# SCH_TwoStep-OPEN-SOURCE_2024-09-30.net
KiCad netlist of a schematic drawn in EasyEDA
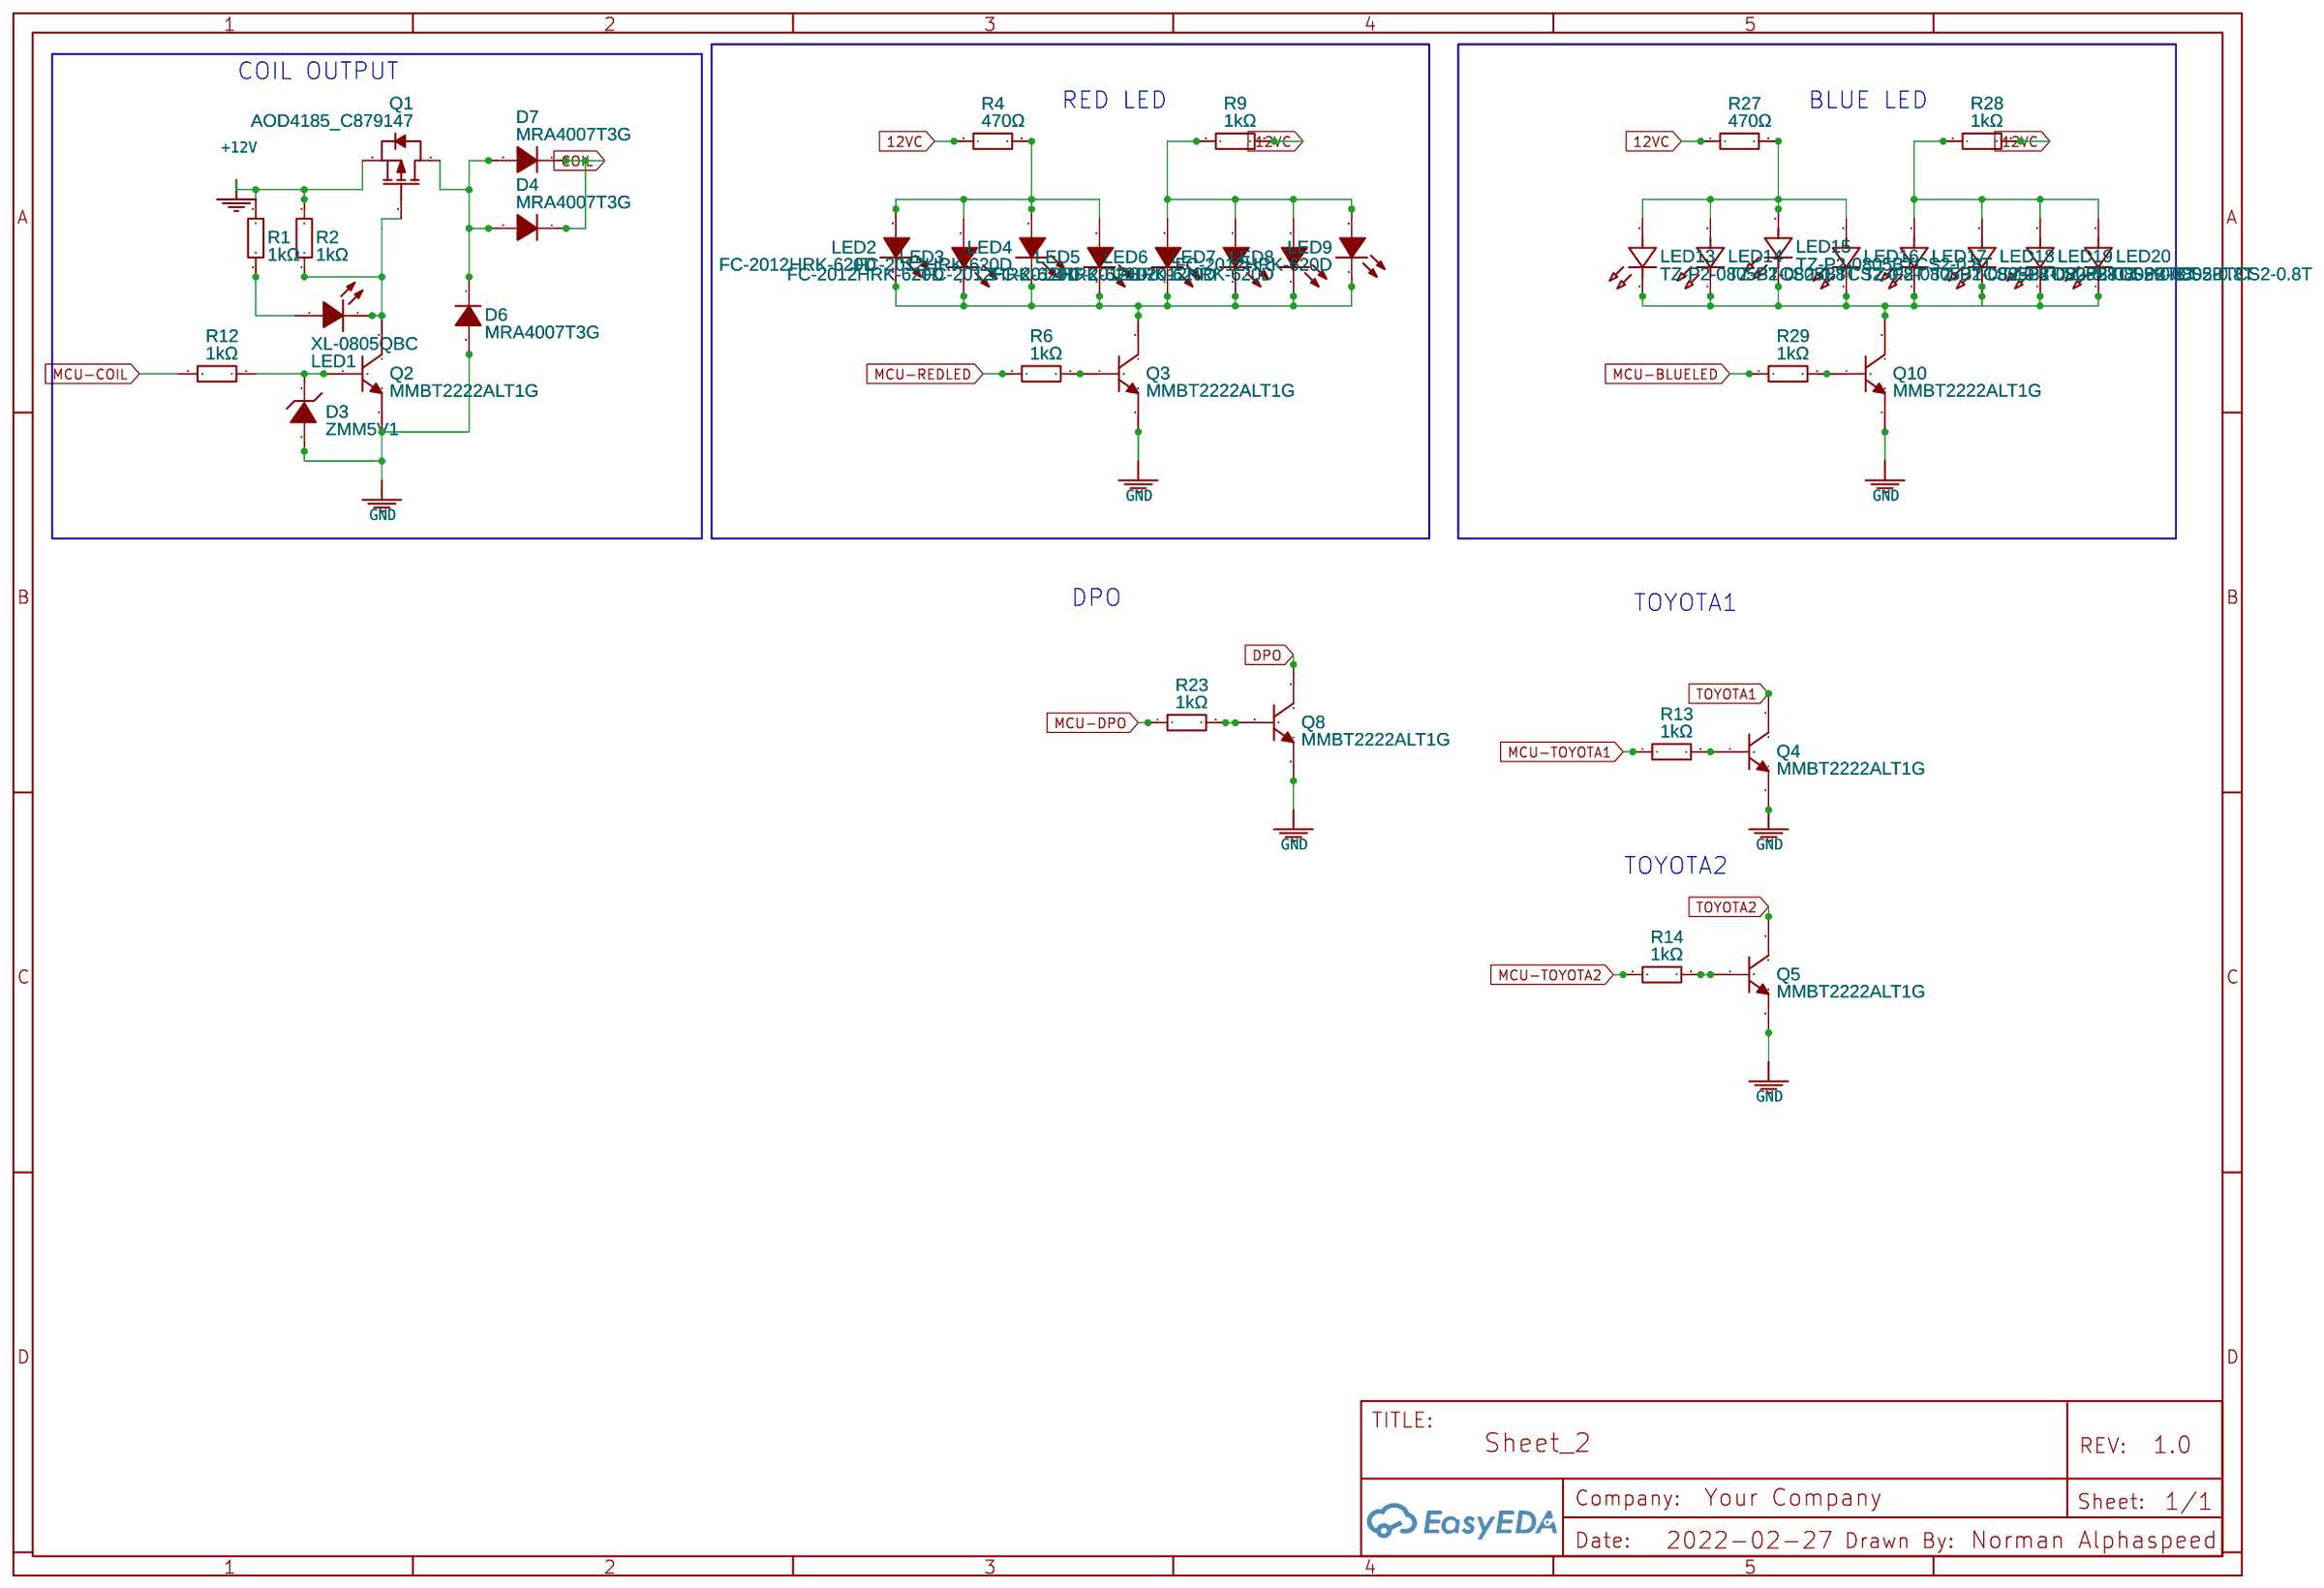
[diagram p0: Outputs]
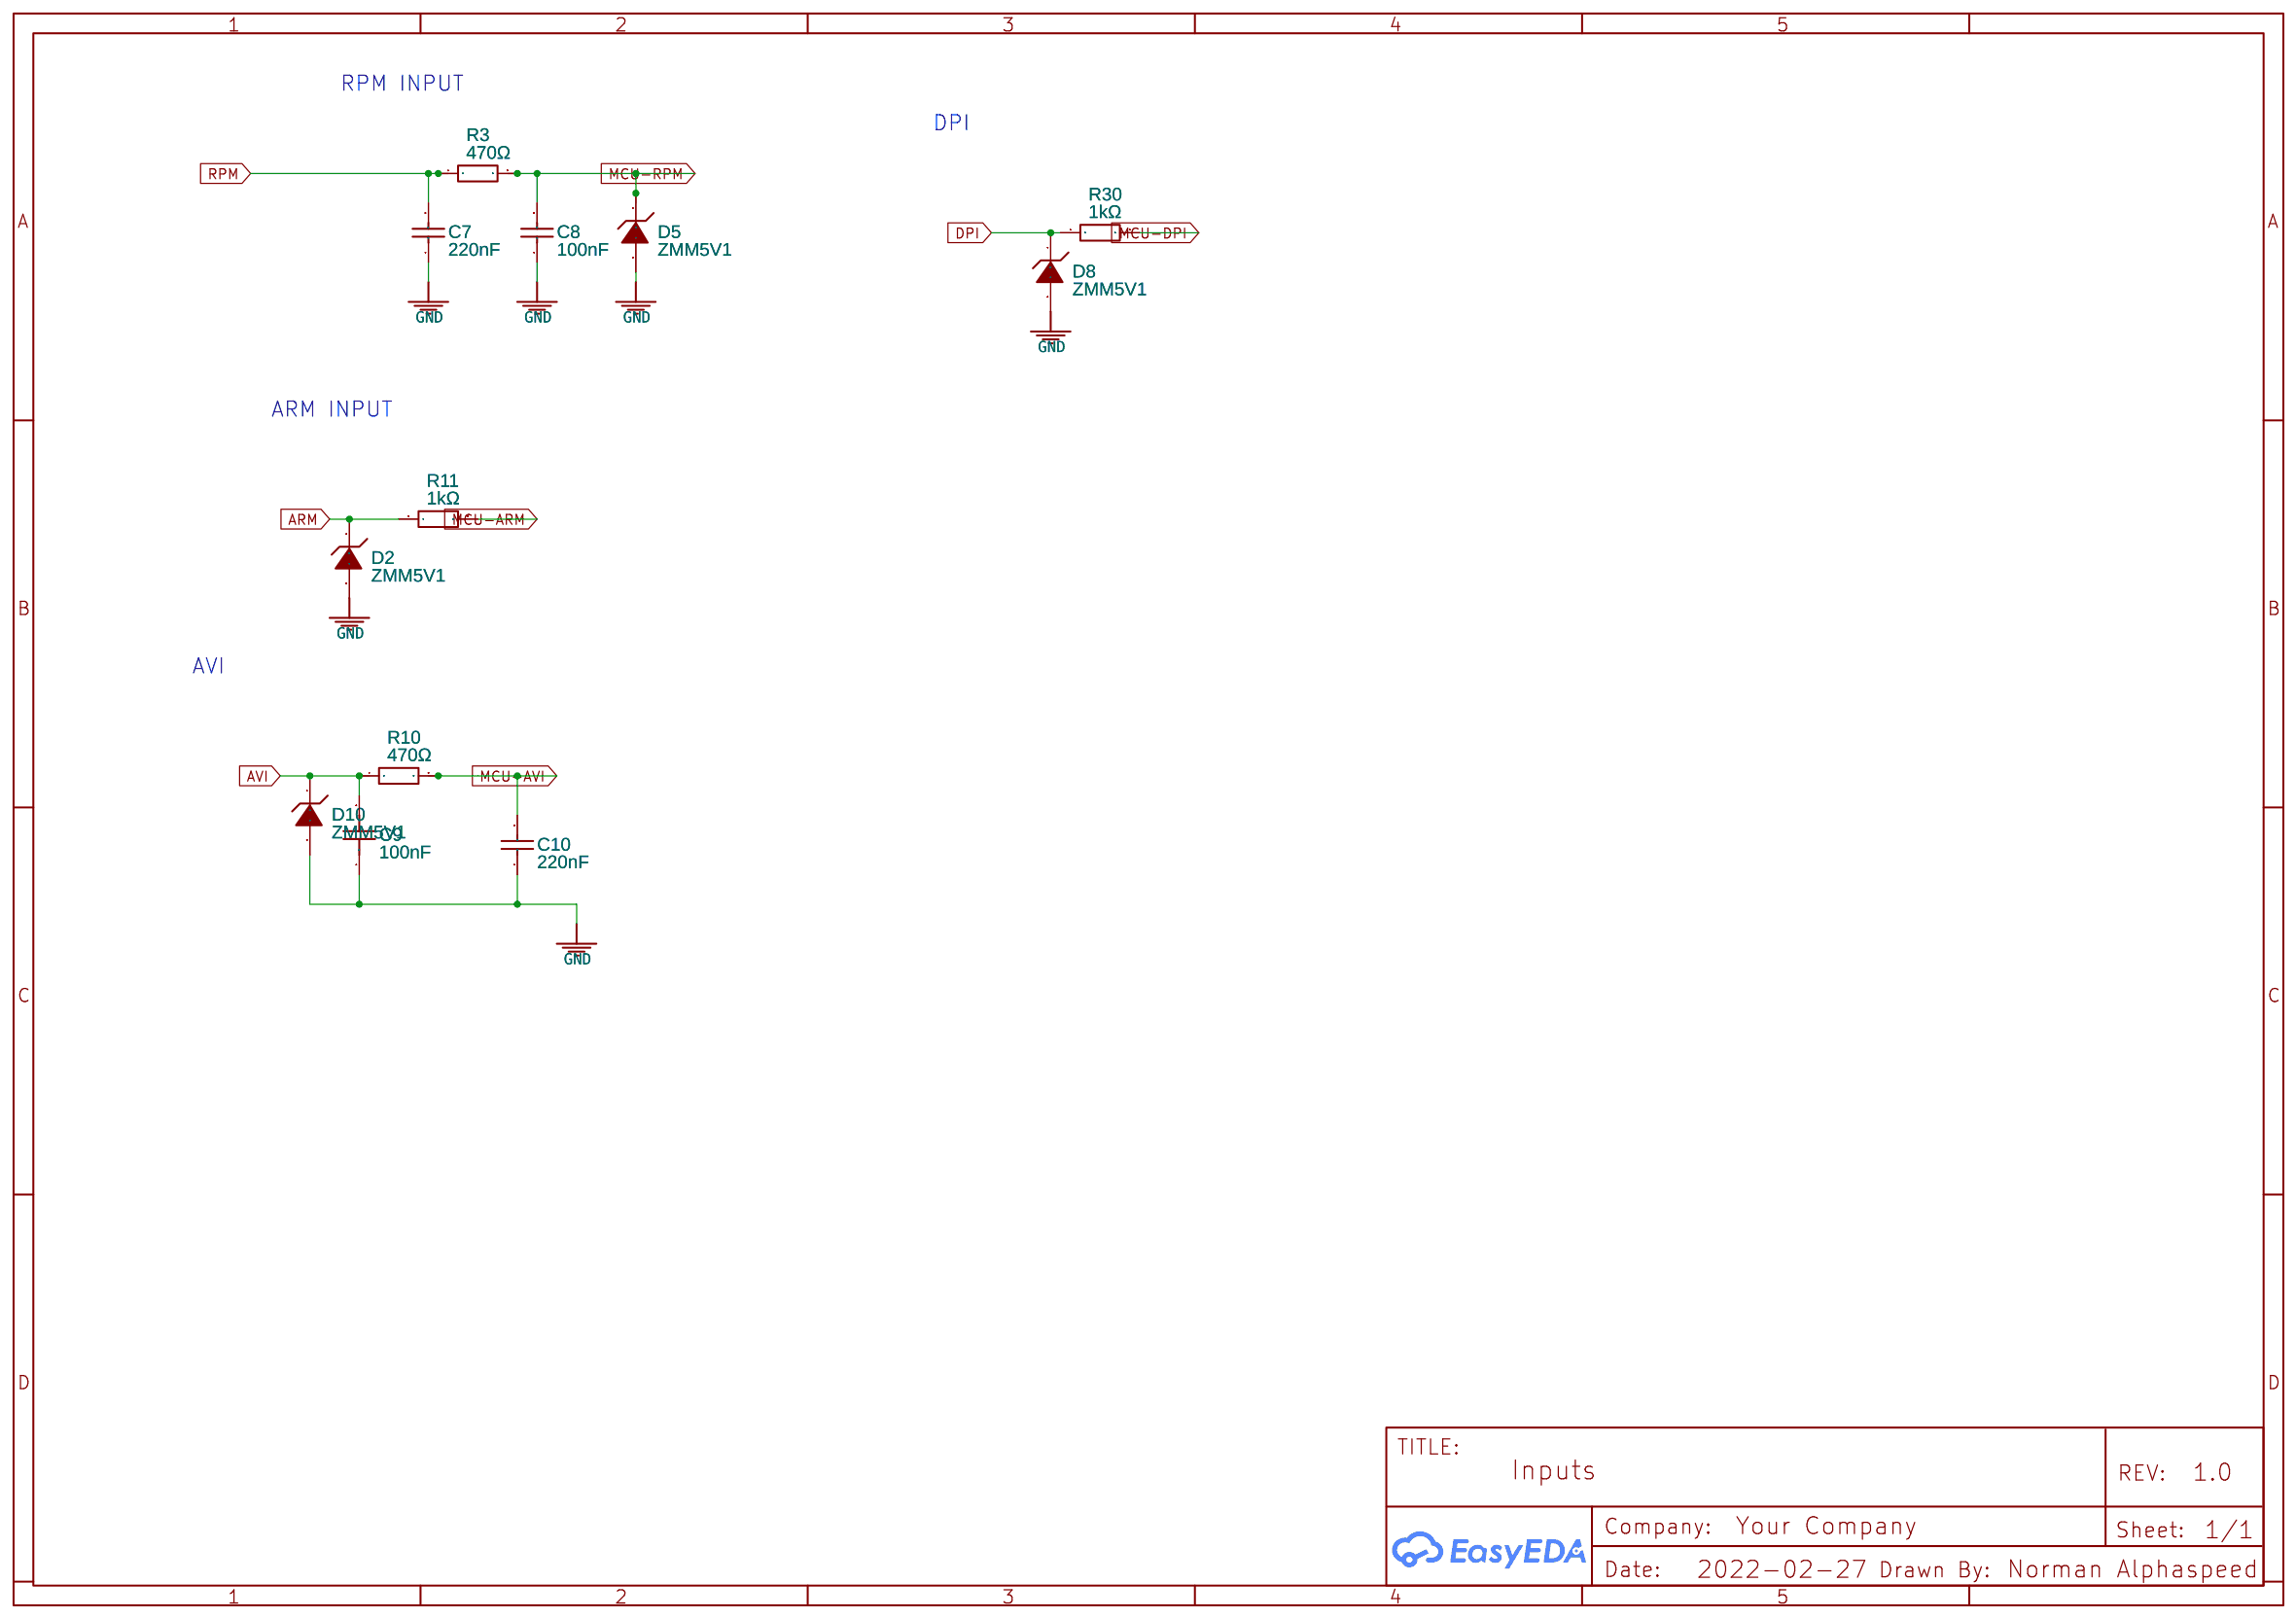
[diagram p1: Inputs]
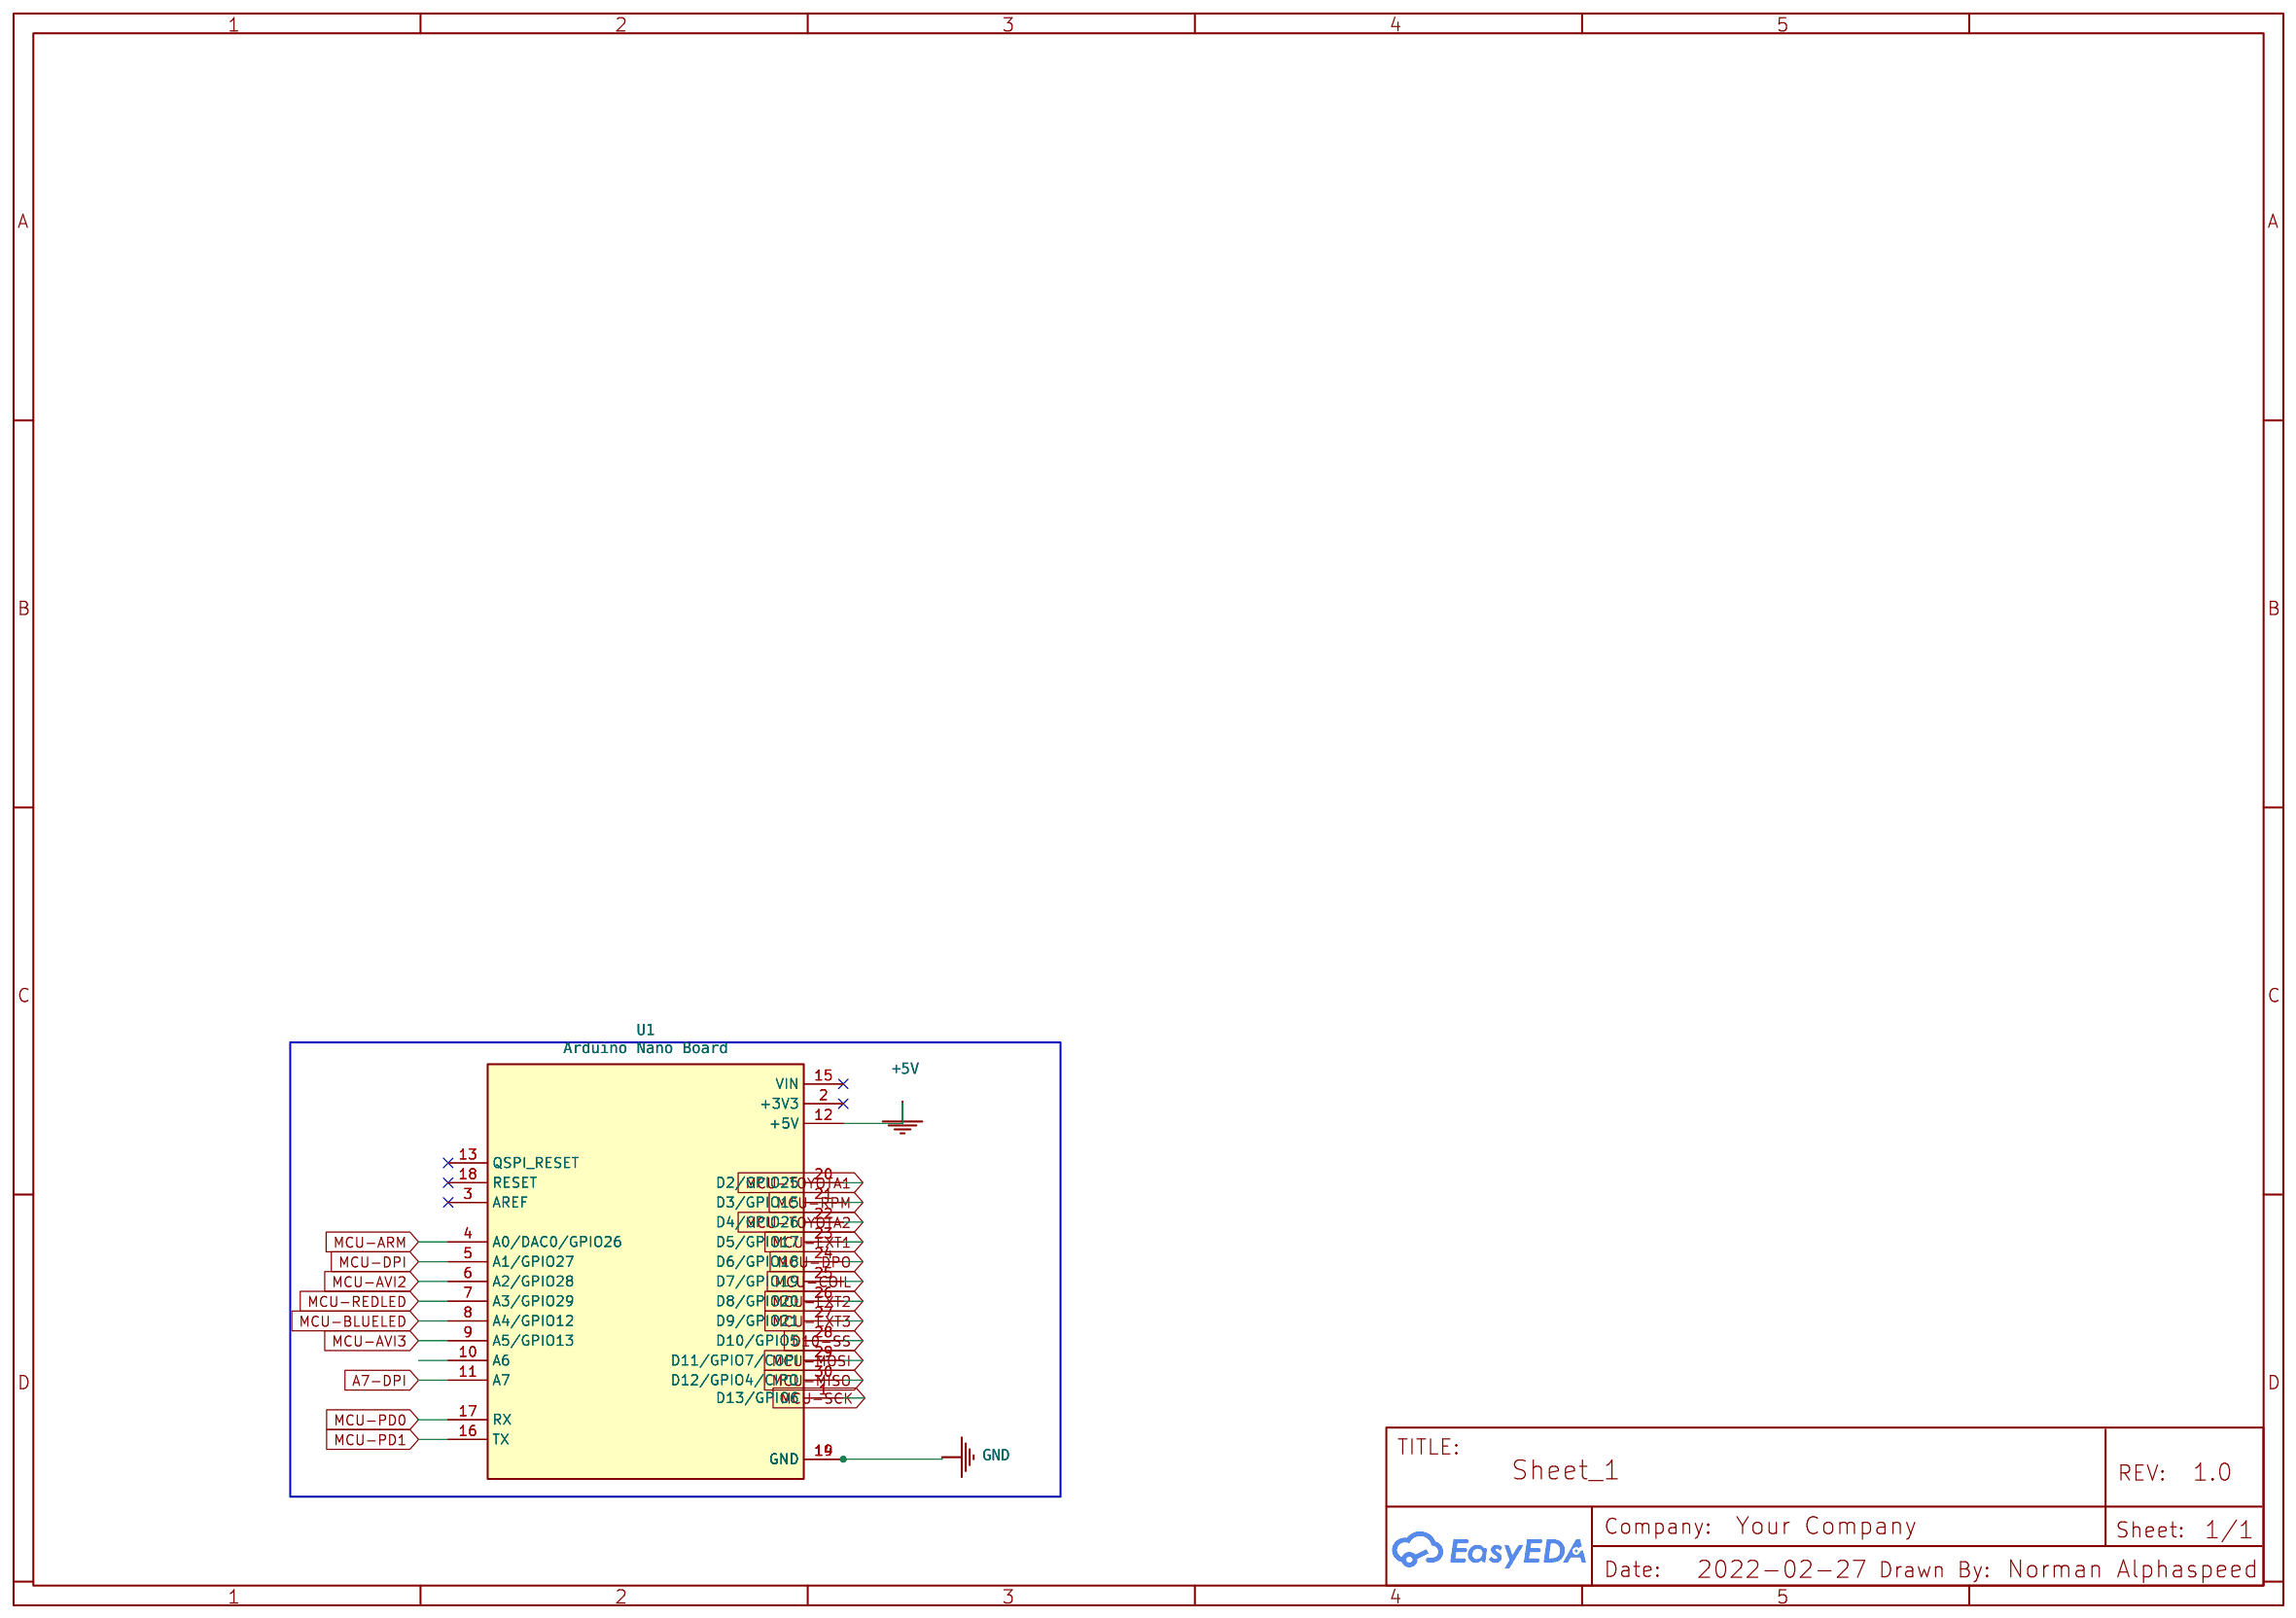
[diagram p2: MCU]
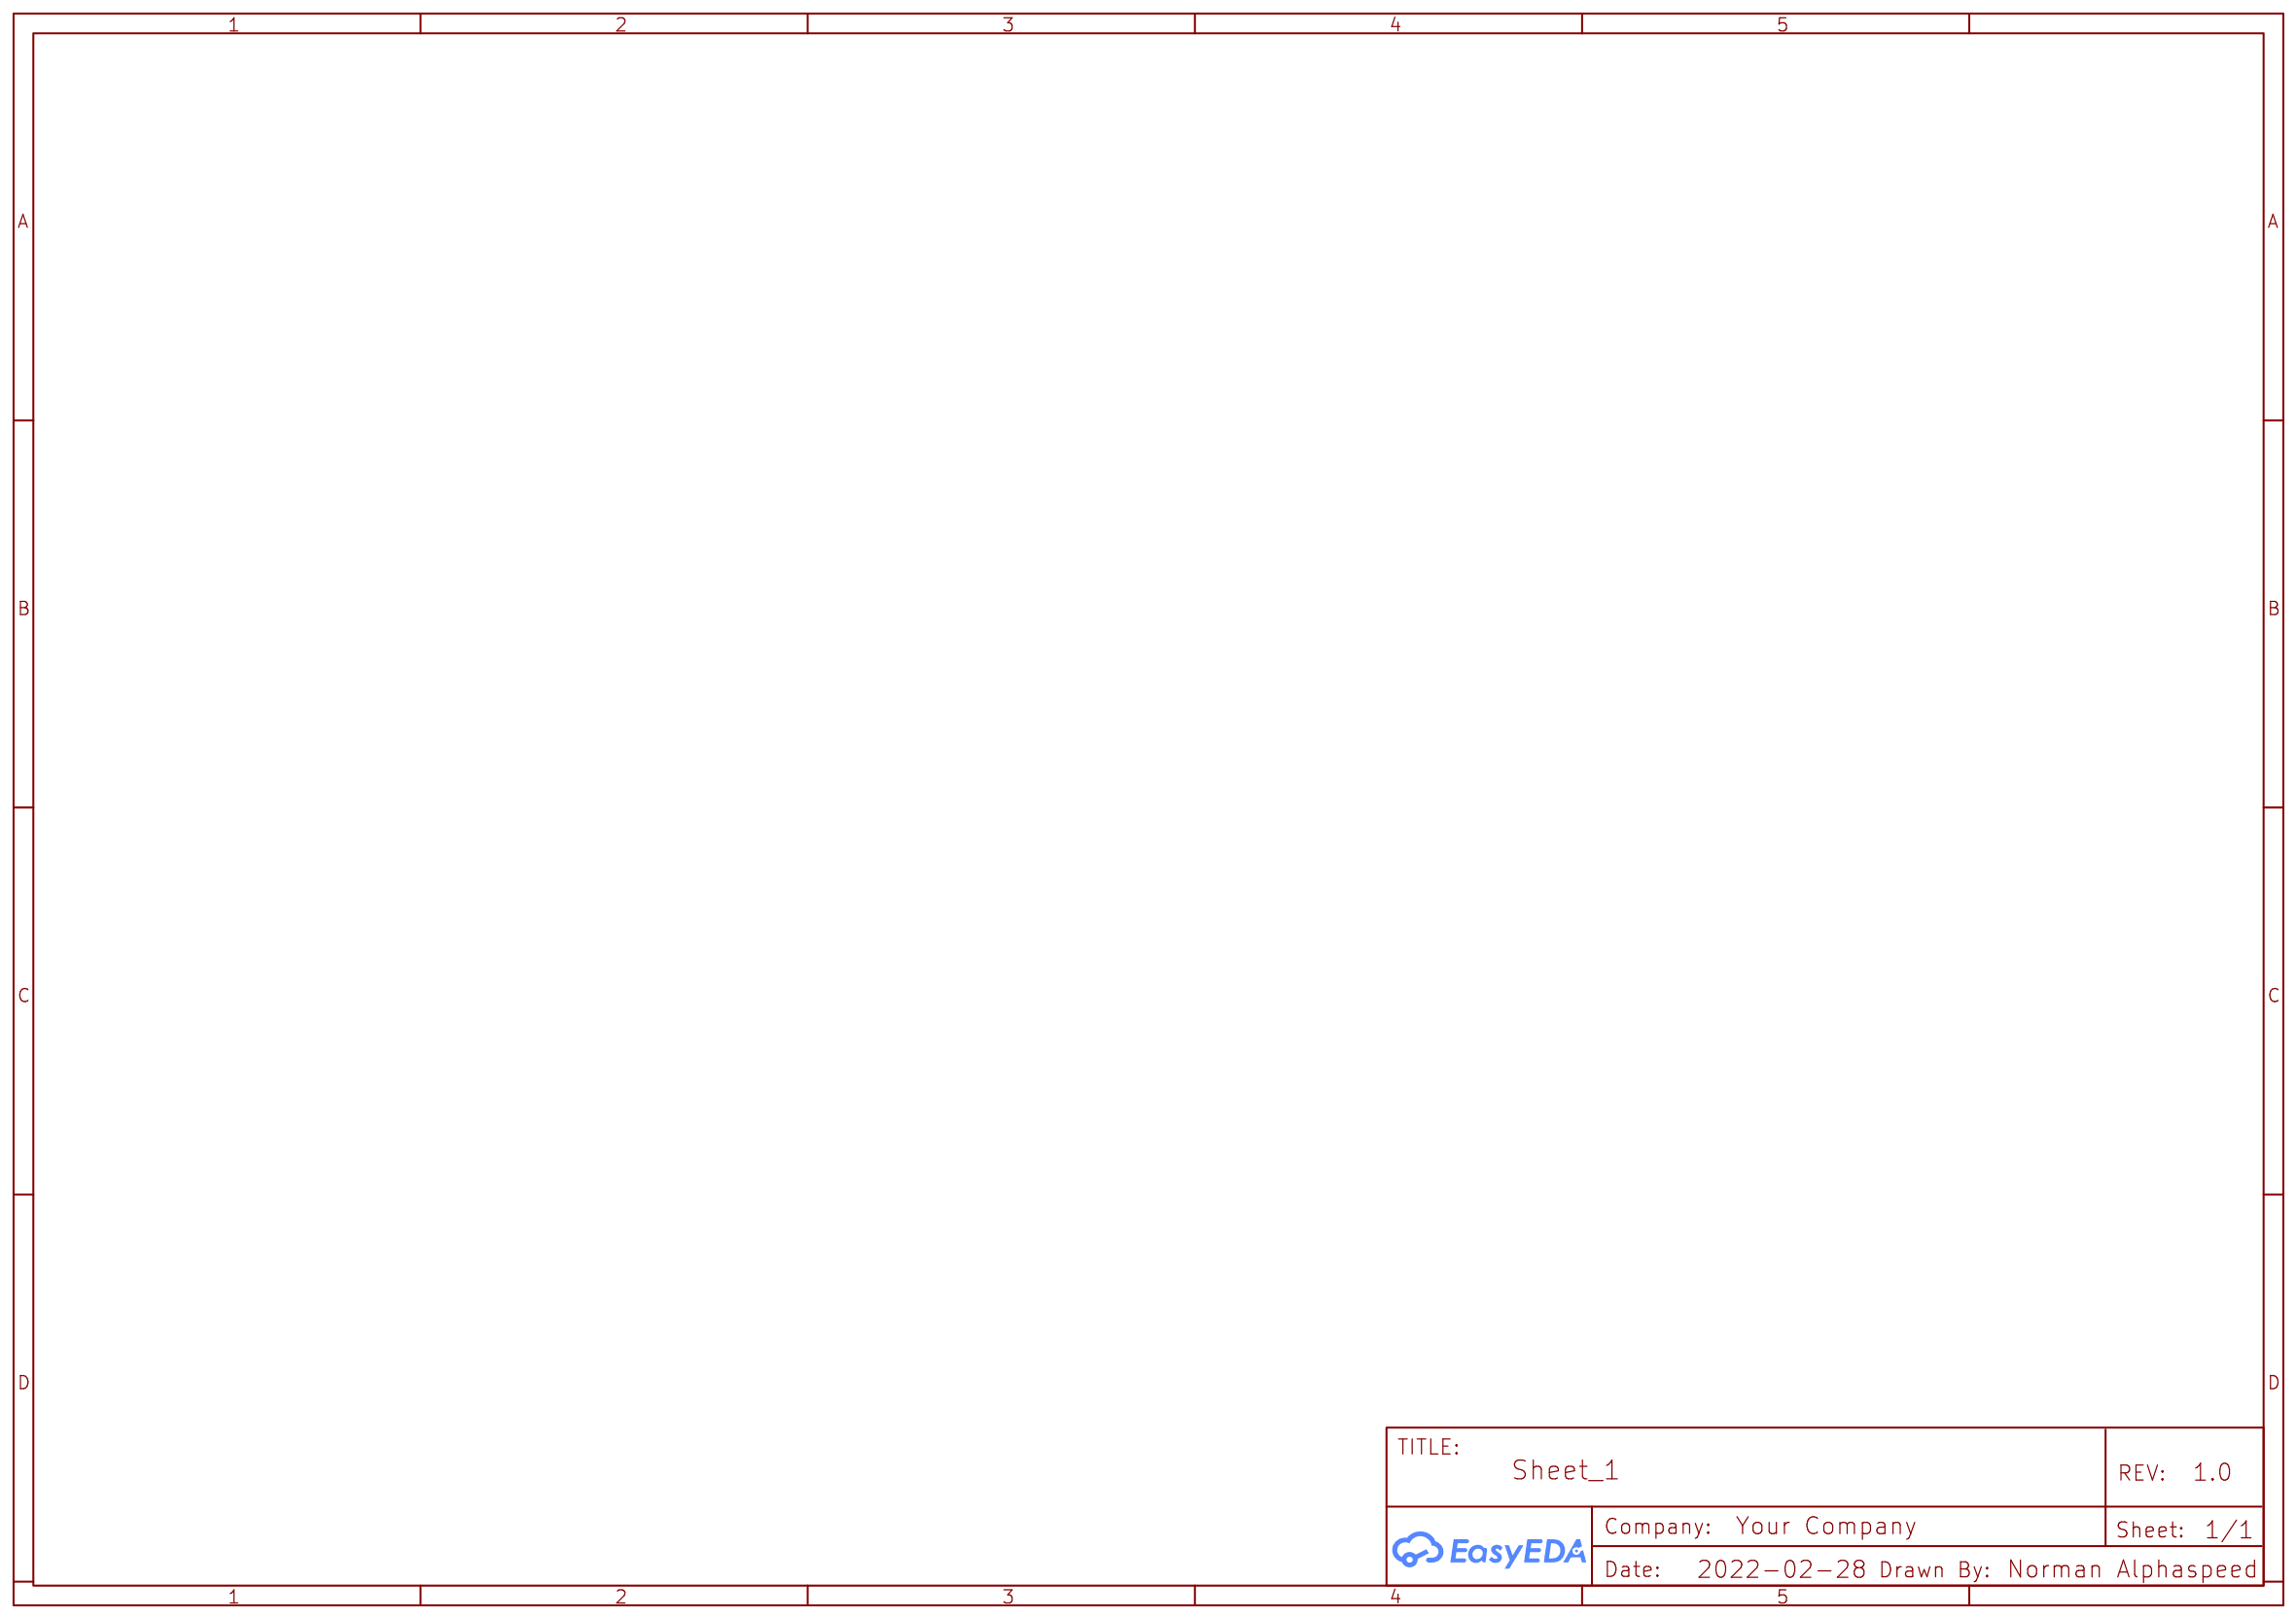
[diagram p3: Comms]
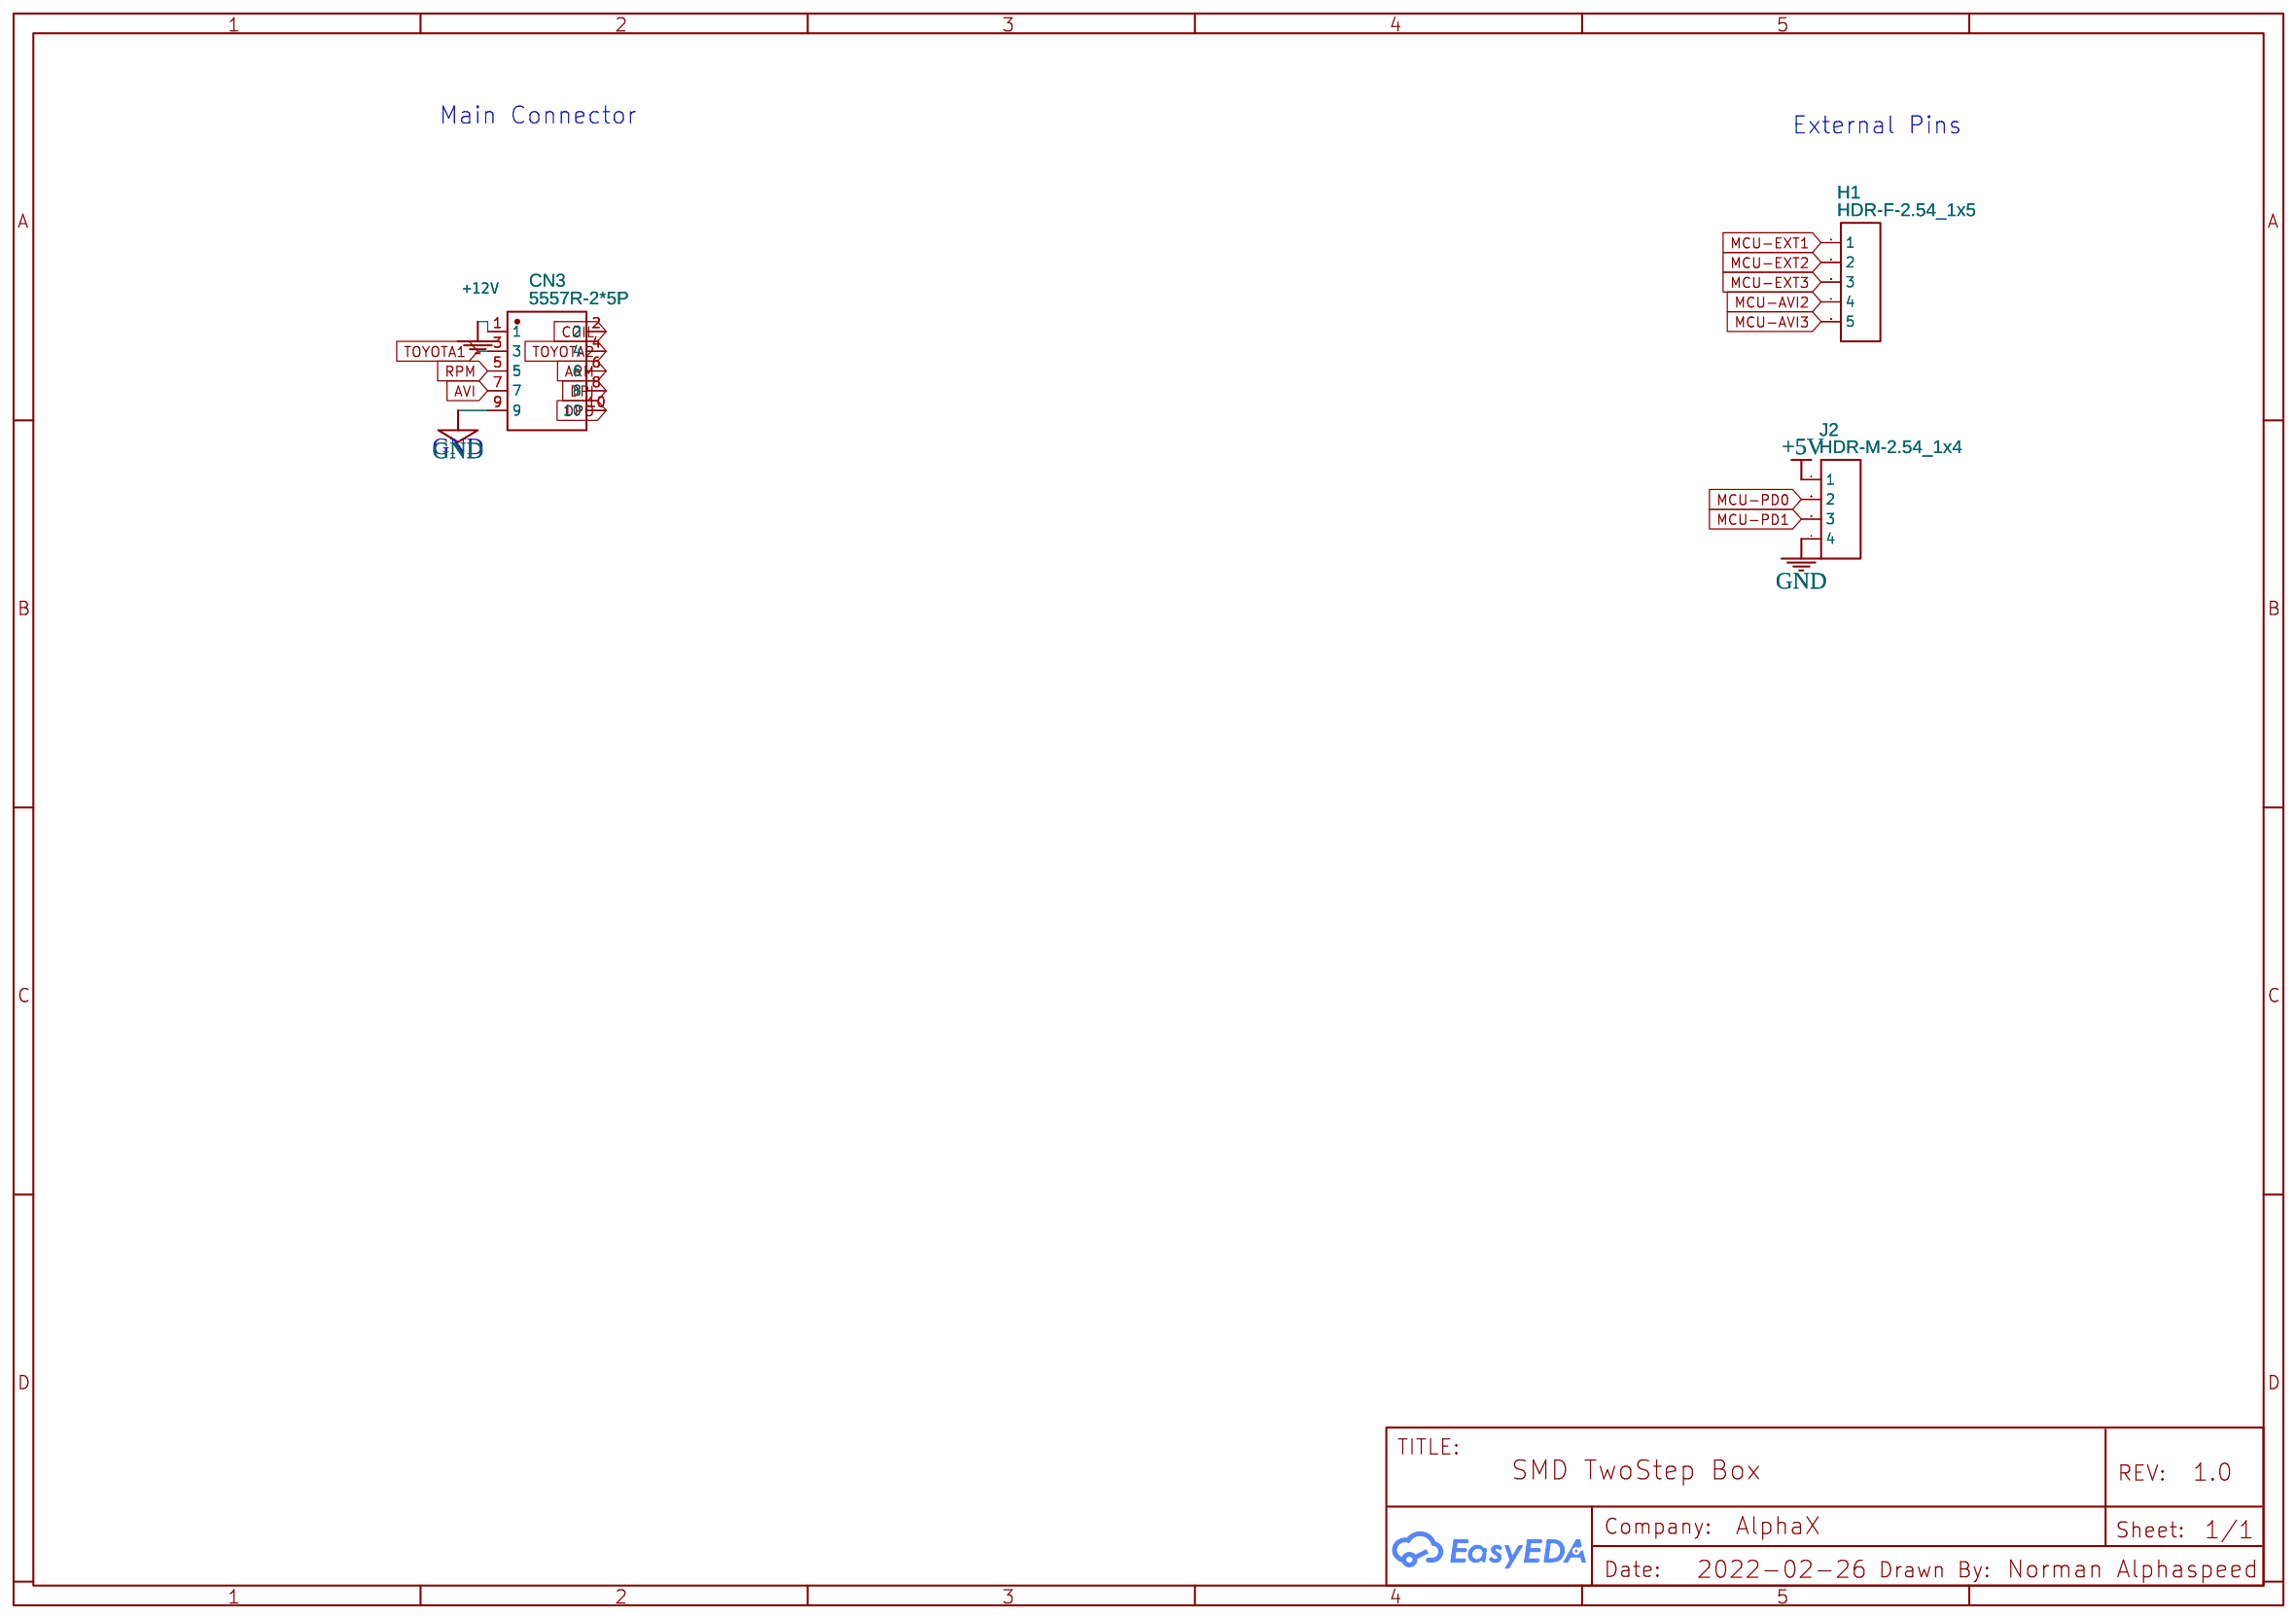
[diagram p4: Connector copy copy]
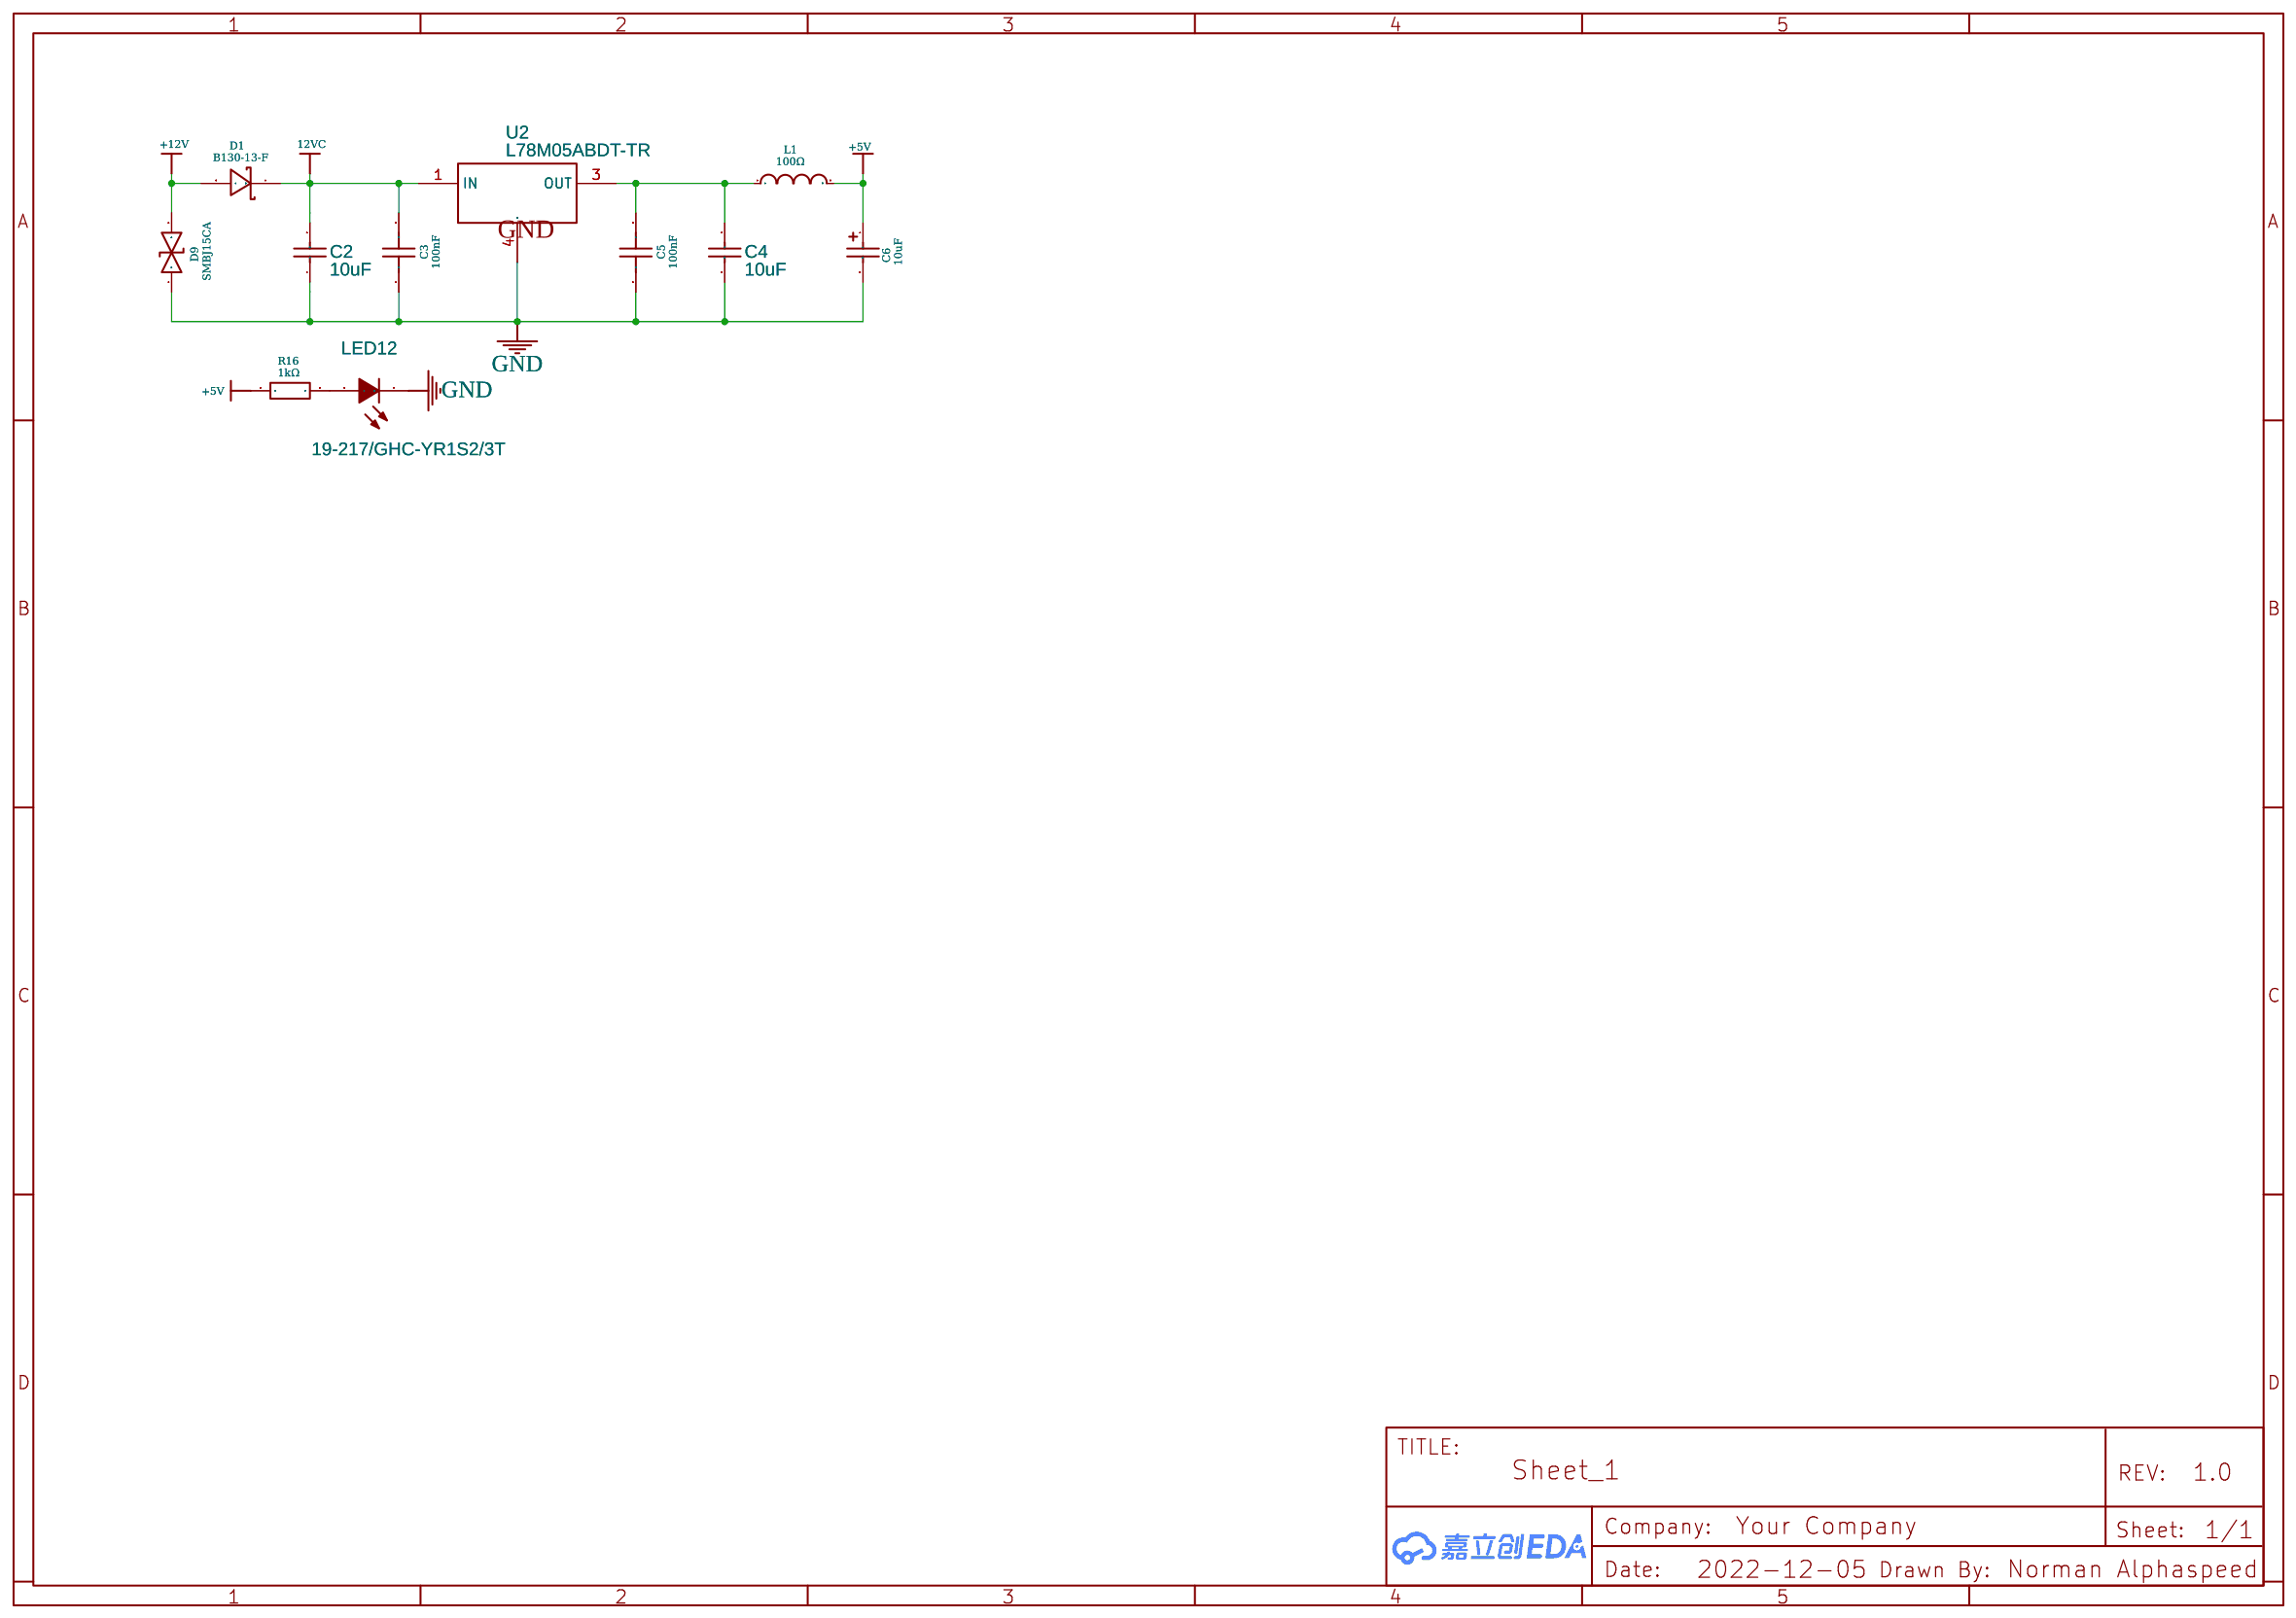
[diagram p5: Power]

(export (version "E")
  (design (tool "Eeschema 10.0.6"))
  (components
    (comp (ref "D3")
      (value "ZMM5V1")
      (fields (field (name "Manufacturer") "SEMTECH"))
      (libsource (lib "") (part "ZMM5V1"))
    )
    (comp (ref "D4")
      (value "MRA4007T3G")
      (fields (field (name "Manufacturer") "ON"))
      (libsource (lib "") (part "MRA4007T3G"))
    )
    (comp (ref "D6")
      (value "MRA4007T3G")
      (fields (field (name "Manufacturer") "ON"))
      (libsource (lib "") (part "MRA4007T3G_1"))
    )
    (comp (ref "D7")
      (value "MRA4007T3G")
      (fields (field (name "Manufacturer") "ON"))
      (libsource (lib "") (part "MRA4007T3G"))
    )
    (comp (ref "LED1")
      (value "XL-0805QBC")
      (fields (field (name "Manufacturer") "KENTO"))
      (libsource (lib "") (part "XL-0805QBC"))
    )
    (comp (ref "LED2")
      (value "FC-2012HRK-620D")
      (fields (field (name "Manufacturer") "NATIONSTAR"))
      (libsource (lib "") (part "FC-2012HRK-620D"))
    )
    (comp (ref "LED3")
      (value "FC-2012HRK-620D")
      (fields (field (name "Manufacturer") "NATIONSTAR"))
      (libsource (lib "") (part "FC-2012HRK-620D"))
    )
    (comp (ref "LED4")
      (value "FC-2012HRK-620D")
      (fields (field (name "Manufacturer") "NATIONSTAR"))
      (libsource (lib "") (part "FC-2012HRK-620D"))
    )
    (comp (ref "LED5")
      (value "FC-2012HRK-620D")
      (fields (field (name "Manufacturer") "NATIONSTAR"))
      (libsource (lib "") (part "FC-2012HRK-620D"))
    )
    (comp (ref "LED6")
      (value "FC-2012HRK-620D")
      (fields (field (name "Manufacturer") "NATIONSTAR"))
      (libsource (lib "") (part "FC-2012HRK-620D"))
    )
    (comp (ref "LED7")
      (value "FC-2012HRK-620D")
      (fields (field (name "Manufacturer") "NATIONSTAR"))
      (libsource (lib "") (part "FC-2012HRK-620D"))
    )
    (comp (ref "LED8")
      (value "FC-2012HRK-620D")
      (fields (field (name "Manufacturer") "NATIONSTAR"))
      (libsource (lib "") (part "FC-2012HRK-620D"))
    )
    (comp (ref "LED9")
      (value "FC-2012HRK-620D")
      (fields (field (name "Manufacturer") "NATIONSTAR"))
      (libsource (lib "") (part "FC-2012HRK-620D"))
    )
    (comp (ref "LED13")
      (value "TZ-P2-0805BTCS2-0.8T")
      (fields (field (name "Manufacturer") "TUOZHAN"))
      (libsource (lib "") (part "TZ-P2-0805BTCS2-0.8T"))
    )
    (comp (ref "LED14")
      (value "TZ-P2-0805BTCS2-0.8T")
      (fields (field (name "Manufacturer") "TUOZHAN"))
      (libsource (lib "") (part "TZ-P2-0805BTCS2-0.8T"))
    )
    (comp (ref "LED15")
      (value "TZ-P2-0805BTCS2-0.8T")
      (fields (field (name "Manufacturer") "TUOZHAN"))
      (libsource (lib "") (part "TZ-P2-0805BTCS2-0.8T"))
    )
    (comp (ref "LED16")
      (value "TZ-P2-0805BTCS2-0.8T")
      (fields (field (name "Manufacturer") "TUOZHAN"))
      (libsource (lib "") (part "TZ-P2-0805BTCS2-0.8T"))
    )
    (comp (ref "LED17")
      (value "TZ-P2-0805BTCS2-0.8T")
      (fields (field (name "Manufacturer") "TUOZHAN"))
      (libsource (lib "") (part "TZ-P2-0805BTCS2-0.8T"))
    )
    (comp (ref "LED18")
      (value "TZ-P2-0805BTCS2-0.8T")
      (fields (field (name "Manufacturer") "TUOZHAN"))
      (libsource (lib "") (part "TZ-P2-0805BTCS2-0.8T"))
    )
    (comp (ref "LED19")
      (value "TZ-P2-0805BTCS2-0.8T")
      (fields (field (name "Manufacturer") "TUOZHAN"))
      (libsource (lib "") (part "TZ-P2-0805BTCS2-0.8T"))
    )
    (comp (ref "LED20")
      (value "TZ-P2-0805BTCS2-0.8T")
      (fields (field (name "Manufacturer") "TUOZHAN"))
      (libsource (lib "") (part "TZ-P2-0805BTCS2-0.8T"))
    )
    (comp (ref "Q1")
      (value "AOD4185_C879147")
      (fields (field (name "Manufacturer Part") "AOD4185") (field (name "Manufacturer") "VBsemi Elec"))
      (libsource (lib "") (part "AOD4185_C879147"))
    )
    (comp (ref "Q2")
      (value "MMBT2222ALT1G")
      (fields (field (name "Manufacturer") "ON"))
      (libsource (lib "") (part "MMBT2222ALT1G"))
    )
    (comp (ref "Q3")
      (value "MMBT2222ALT1G")
      (fields (field (name "Manufacturer") "ON"))
      (libsource (lib "") (part "MMBT2222ALT1G"))
    )
    (comp (ref "Q4")
      (value "MMBT2222ALT1G")
      (fields (field (name "Manufacturer") "ON"))
      (libsource (lib "") (part "MMBT2222ALT1G"))
    )
    (comp (ref "Q5")
      (value "MMBT2222ALT1G")
      (fields (field (name "Manufacturer") "ON"))
      (libsource (lib "") (part "MMBT2222ALT1G"))
    )
    (comp (ref "Q8")
      (value "MMBT2222ALT1G")
      (fields (field (name "Manufacturer") "ON"))
      (libsource (lib "") (part "MMBT2222ALT1G"))
    )
    (comp (ref "Q10")
      (value "MMBT2222ALT1G")
      (fields (field (name "Manufacturer") "ON"))
      (libsource (lib "") (part "MMBT2222ALT1G"))
    )
    (comp (ref "R1")
      (value "1kΩ")
      (fields (field (name "Manufacturer Part") "0603WAF1001T5E") (field (name "Manufacturer") "UniOhm"))
      (libsource (lib "") (part "0603WAF1001T5E"))
    )
    (comp (ref "R2")
      (value "1kΩ")
      (fields (field (name "Manufacturer Part") "0603WAF1001T5E") (field (name "Manufacturer") "UniOhm"))
      (libsource (lib "") (part "0603WAF1001T5E"))
    )
    (comp (ref "R4")
      (value "470Ω")
      (fields (field (name "Manufacturer Part") "0805W8F4700T5E") (field (name "Manufacturer") "UniOhm"))
      (libsource (lib "") (part "0805W8F4700T5E"))
    )
    (comp (ref "R6")
      (value "1kΩ")
      (fields (field (name "Manufacturer Part") "0603WAF1001T5E") (field (name "Manufacturer") "UniOhm"))
      (libsource (lib "") (part "0603WAF1001T5E_1"))
    )
    (comp (ref "R9")
      (value "1kΩ")
      (fields (field (name "Manufacturer Part") "0603WAF1001T5E") (field (name "Manufacturer") "UniOhm"))
      (libsource (lib "") (part "0603WAF1001T5E_1"))
    )
    (comp (ref "R12")
      (value "1kΩ")
      (fields (field (name "Manufacturer Part") "0603WAF1001T5E") (field (name "Manufacturer") "UniOhm"))
      (libsource (lib "") (part "0603WAF1001T5E_2"))
    )
    (comp (ref "R13")
      (value "1kΩ")
      (fields (field (name "Manufacturer Part") "0603WAF1001T5E") (field (name "Manufacturer") "UniOhm"))
      (libsource (lib "") (part "0603WAF1001T5E_1"))
    )
    (comp (ref "R14")
      (value "1kΩ")
      (fields (field (name "Manufacturer Part") "0603WAF1001T5E") (field (name "Manufacturer") "UniOhm"))
      (libsource (lib "") (part "0603WAF1001T5E_1"))
    )
    (comp (ref "R23")
      (value "1kΩ")
      (fields (field (name "Manufacturer Part") "0603WAF1001T5E") (field (name "Manufacturer") "UniOhm"))
      (libsource (lib "") (part "0603WAF1001T5E_1"))
    )
    (comp (ref "R27")
      (value "470Ω")
      (fields (field (name "Manufacturer Part") "0805W8F4700T5E") (field (name "Manufacturer") "UniOhm"))
      (libsource (lib "") (part "0805W8F4700T5E"))
    )
    (comp (ref "R28")
      (value "1kΩ")
      (fields (field (name "Manufacturer Part") "0603WAF1001T5E") (field (name "Manufacturer") "UniOhm"))
      (libsource (lib "") (part "0603WAF1001T5E_1"))
    )
    (comp (ref "R29")
      (value "1kΩ")
      (fields (field (name "Manufacturer Part") "0603WAF1001T5E") (field (name "Manufacturer") "UniOhm"))
      (libsource (lib "") (part "0603WAF1001T5E_1"))
    )
    (comp (ref "C7")
      (value "220nF")
      (fields (field (name "Manufacturer Part") "CL21B224KBFNNNE") (field (name "Manufacturer") "SAMSUNG"))
      (libsource (lib "") (part "CL21B224KBFNNNE"))
    )
    (comp (ref "C8")
      (value "100nF")
      (fields (field (name "Manufacturer Part") "CC0805KRX7R9BB104") (field (name "Manufacturer") "YAGEO"))
      (libsource (lib "") (part "CC0805KRX7R9BB104"))
    )
    (comp (ref "C9")
      (value "100nF")
      (fields (field (name "Manufacturer Part") "CC0603KRX7R9BB104") (field (name "Manufacturer") "YAGEO"))
      (libsource (lib "") (part "CC0603KRX7R9BB104"))
    )
    (comp (ref "C10")
      (value "220nF")
      (fields (field (name "Manufacturer Part") "CL10B224KA8NNNC") (field (name "Manufacturer") "SAMSUNG"))
      (libsource (lib "") (part "CL10B224KA8NNNC"))
    )
    (comp (ref "D2")
      (value "ZMM5V1")
      (fields (field (name "Manufacturer") "SEMTECH"))
      (libsource (lib "") (part "ZMM5V1"))
    )
    (comp (ref "D5")
      (value "ZMM5V1")
      (fields (field (name "Manufacturer") "SEMTECH"))
      (libsource (lib "") (part "ZMM5V1"))
    )
    (comp (ref "D8")
      (value "ZMM5V1")
      (fields (field (name "Manufacturer") "SEMTECH"))
      (libsource (lib "") (part "ZMM5V1"))
    )
    (comp (ref "D10")
      (value "ZMM5V1")
      (fields (field (name "Manufacturer") "SEMTECH"))
      (libsource (lib "") (part "ZMM5V1"))
    )
    (comp (ref "R3")
      (value "470Ω")
      (fields (field (name "Manufacturer Part") "0805W8F4700T5E") (field (name "Manufacturer") "UniOhm"))
      (libsource (lib "") (part "0805W8F4700T5E"))
    )
    (comp (ref "R10")
      (value "470Ω")
      (fields (field (name "Manufacturer Part") "0805W8F4700T5E") (field (name "Manufacturer") "UniOhm"))
      (libsource (lib "") (part "0805W8F4700T5E"))
    )
    (comp (ref "R11")
      (value "1kΩ")
      (fields (field (name "Manufacturer Part") "0603WAF1001T5E") (field (name "Manufacturer") "UniOhm"))
      (libsource (lib "") (part "0603WAF1001T5E"))
    )
    (comp (ref "R30")
      (value "1kΩ")
      (fields (field (name "Manufacturer Part") "0603WAF1001T5E") (field (name "Manufacturer") "UniOhm"))
      (libsource (lib "") (part "0603WAF1001T5E"))
    )
    (comp (ref "U1") (value "Arduino Nano Board") (libsource (lib "") (part "Unknown_320_-174")))
    (comp (ref "CN3")
      (value "5557R-2*5P")
      (fields (field (name "Manufacturer") "Ckmtw"))
      (libsource (lib "") (part "5557R-2*5P"))
    )
    (comp (ref "H1") (value "HDR-F-2.54_1x5") (libsource (lib "") (part "HDR-F-2.54_1x5")))
    (comp (ref "J2") (value "HDR-M-2.54_1x4") (libsource (lib "") (part "HDR-M-2.54_1x4")))
    (comp (ref "C2")
      (value "10uF")
      (fields (field (name "Manufacturer Part") "CL31A106KBHNNNE") (field (name "Manufacturer") "SAMSUNG"))
      (libsource (lib "") (part "CL31A106KBHNNNE"))
    )
    (comp (ref "C3")
      (value "100nF")
      (fields (field (name "Manufacturer Part") "CC0603KRX7R9BB104") (field (name "Manufacturer") "YAGEO"))
      (libsource (lib "") (part "CC0603KRX7R9BB104"))
    )
    (comp (ref "C4")
      (value "10uF")
      (fields (field (name "Manufacturer Part") "CL31A106KBHNNNE") (field (name "Manufacturer") "SAMSUNG"))
      (libsource (lib "") (part "CL31A106KBHNNNE"))
    )
    (comp (ref "C5")
      (value "100nF")
      (fields (field (name "Manufacturer Part") "CC0603KRX7R9BB104") (field (name "Manufacturer") "YAGEO"))
      (libsource (lib "") (part "CC0603KRX7R9BB104"))
    )
    (comp (ref "C6")
      (value "10uF")
      (fields (field (name "Manufacturer Part") "TAJA106K016RNJ") (field (name "Manufacturer") "AVX"))
      (libsource (lib "") (part "TAJA106K016RNJ"))
    )
    (comp (ref "D1")
      (value "B130-13-F")
      (fields (field (name "Manufacturer") "DIODES"))
      (libsource (lib "") (part "B130-13-F"))
    )
    (comp (ref "D9")
      (value "SMBJ15CA")
      (fields (field (name "Manufacturer") "MDD"))
      (libsource (lib "") (part "SMBJ15CA-C113989"))
    )
    (comp (ref "L1")
      (value "100Ω")
      (fields (field (name "Manufacturer Part") "GZ2012D101TF") (field (name "Manufacturer") "Sunlord"))
      (libsource (lib "") (part "GZ2012D101TF"))
    )
    (comp (ref "LED12")
      (value "19-217/GHC-YR1S2/3T")
      (fields (field (name "Manufacturer") "EVERLIGHT(亿光)"))
      (libsource (lib "") (part "19-217/GHC-YR1S2/3T"))
    )
    (comp (ref "R16")
      (value "1kΩ")
      (fields (field (name "Manufacturer Part") "0402WGF1001TCE") (field (name "Manufacturer") "UniOhm"))
      (libsource (lib "") (part "0402WGF1001TCE"))
    )
    (comp (ref "U2")
      (value "L78M05ABDT-TR")
      (fields (field (name "Manufacturer") "STMicroelectronics"))
      (libsource (lib "") (part "L78M05ABDT-TR"))
    )
  )
  (nets
    (net (code "1") (name "+5V") (class "Default")
      (node (ref "C6") (pin "1") (pinfunction "1_1") (pintype "input"))
      (node (ref "J2") (pin "1") (pinfunction "1_1") (pintype "unspecified"))
      (node (ref "L1") (pin "2") (pinfunction "2_2") (pintype "unspecified"))
      (node (ref "R16") (pin "1") (pinfunction "1_1") (pintype "input"))
      (node (ref "U1") (pin "12") (pinfunction "+5V_12") (pintype "bidirectional"))
    )
    (net (code "2") (name "+12V") (class "Default")
      (node (ref "CN3") (pin "1") (pinfunction "1_1") (pintype "unspecified"))
      (node (ref "D1") (pin "2") (pinfunction "A_2") (pintype "unspecified"))
      (node (ref "D9") (pin "2") (pinfunction "2_2") (pintype "unspecified"))
      (node (ref "Q1") (pin "3") (pinfunction "S_3") (pintype "unspecified"))
      (node (ref "R1") (pin "2") (pinfunction "2_2") (pintype "input"))
      (node (ref "R2") (pin "2") (pinfunction "2_2") (pintype "input"))
    )
    (net (code "3") (name "12VC") (class "Default")
      (node (ref "C2") (pin "2") (pinfunction "2_2") (pintype "input"))
      (node (ref "C3") (pin "2") (pinfunction "2_2") (pintype "unspecified"))
      (node (ref "D1") (pin "1") (pinfunction "C_1") (pintype "unspecified"))
      (node (ref "R27") (pin "1") (pinfunction "1_1") (pintype "input"))
      (node (ref "R28") (pin "2") (pinfunction "2_2") (pintype "input"))
      (node (ref "R4") (pin "1") (pinfunction "1_1") (pintype "input"))
      (node (ref "R9") (pin "2") (pinfunction "2_2") (pintype "input"))
      (node (ref "U2") (pin "1") (pinfunction "IN_1") (pintype "passive"))
    )
    (net (code "4") (name "A7-DPI") (class "Default")
      (node (ref "U1") (pin "11") (pinfunction "A7_11") (pintype "bidirectional"))
    )
    (net (code "5") (name "ARM") (class "Default")
      (node (ref "CN3") (pin "6") (pinfunction "6_6") (pintype "unspecified"))
      (node (ref "D2") (pin "1") (pinfunction "C_1") (pintype "unspecified"))
      (node (ref "R11") (pin "1") (pinfunction "1_1") (pintype "input"))
    )
    (net (code "6") (name "AVI") (class "Default")
      (node (ref "C9") (pin "2") (pinfunction "2_2") (pintype "unspecified"))
      (node (ref "CN3") (pin "7") (pinfunction "7_7") (pintype "unspecified"))
      (node (ref "D10") (pin "1") (pinfunction "C_1") (pintype "unspecified"))
      (node (ref "R10") (pin "1") (pinfunction "1_1") (pintype "input"))
    )
    (net (code "7") (name "COIL") (class "Default")
      (node (ref "CN3") (pin "2") (pinfunction "2_2") (pintype "unspecified"))
      (node (ref "D4") (pin "1") (pinfunction "C_1") (pintype "unspecified"))
      (node (ref "D7") (pin "1") (pinfunction "C_1") (pintype "unspecified"))
    )
    (net (code "8") (name "D10-SS") (class "Default")
      (node (ref "U1") (pin "28") (pinfunction "D10/GPIO5_28") (pintype "bidirectional"))
    )
    (net (code "9") (name "DPI") (class "Default")
      (node (ref "CN3") (pin "8") (pinfunction "8_8") (pintype "unspecified"))
      (node (ref "D8") (pin "1") (pinfunction "C_1") (pintype "unspecified"))
      (node (ref "R30") (pin "1") (pinfunction "1_1") (pintype "input"))
    )
    (net (code "10") (name "DPO") (class "Default")
      (node (ref "CN3") (pin "10") (pinfunction "10_10") (pintype "unspecified"))
      (node (ref "Q8") (pin "3") (pinfunction "C_3") (pintype "unspecified"))
    )
    (net (code "11") (name "GND") (class "Default")
      (node (ref "C10") (pin "1") (pinfunction "1_1") (pintype "input"))
      (node (ref "C2") (pin "1") (pinfunction "1_1") (pintype "input"))
      (node (ref "C3") (pin "1") (pinfunction "1_1") (pintype "unspecified"))
      (node (ref "C4") (pin "1") (pinfunction "1_1") (pintype "input"))
      (node (ref "C5") (pin "1") (pinfunction "1_1") (pintype "unspecified"))
      (node (ref "C6") (pin "2") (pinfunction "2_2") (pintype "input"))
      (node (ref "C7") (pin "1") (pinfunction "1_1") (pintype "input"))
      (node (ref "C8") (pin "1") (pinfunction "1_1") (pintype "input"))
      (node (ref "C9") (pin "1") (pinfunction "1_1") (pintype "unspecified"))
      (node (ref "CN3") (pin "9") (pinfunction "9_9") (pintype "unspecified"))
      (node (ref "D10") (pin "2") (pinfunction "A_2") (pintype "unspecified"))
      (node (ref "D2") (pin "2") (pinfunction "A_2") (pintype "unspecified"))
      (node (ref "D3") (pin "2") (pinfunction "A_2") (pintype "unspecified"))
      (node (ref "D5") (pin "2") (pinfunction "A_2") (pintype "unspecified"))
      (node (ref "D6") (pin "2") (pinfunction "A_2") (pintype "unspecified"))
      (node (ref "D8") (pin "2") (pinfunction "A_2") (pintype "unspecified"))
      (node (ref "D9") (pin "1") (pinfunction "1_1") (pintype "unspecified"))
      (node (ref "J2") (pin "4") (pinfunction "4_4") (pintype "unspecified"))
      (node (ref "LED12") (pin "1") (pinfunction "C_1") (pintype "input"))
      (node (ref "Q10") (pin "2") (pinfunction "E_2") (pintype "unspecified"))
      (node (ref "Q2") (pin "2") (pinfunction "E_2") (pintype "unspecified"))
      (node (ref "Q3") (pin "2") (pinfunction "E_2") (pintype "unspecified"))
      (node (ref "Q4") (pin "2") (pinfunction "E_2") (pintype "unspecified"))
      (node (ref "Q5") (pin "2") (pinfunction "E_2") (pintype "unspecified"))
      (node (ref "Q8") (pin "2") (pinfunction "E_2") (pintype "unspecified"))
      (node (ref "U1") (pin "14") (pinfunction "GND_14") (pintype "bidirectional"))
      (node (ref "U1") (pin "19") (pinfunction "GND_19") (pintype "bidirectional"))
      (node (ref "U2") (pin "4") (pinfunction "GND_4") (pintype "passive"))
    )
    (net (code "12") (name "MCU-ARM") (class "Default")
      (node (ref "R11") (pin "2") (pinfunction "2_2") (pintype "input"))
      (node (ref "U1") (pin "4") (pinfunction "A0/DAC0/GPIO26_4") (pintype "bidirectional"))
    )
    (net (code "13") (name "MCU-AVI") (class "Default")
      (node (ref "C10") (pin "2") (pinfunction "2_2") (pintype "input"))
      (node (ref "R10") (pin "2") (pinfunction "2_2") (pintype "input"))
    )
    (net (code "14") (name "MCU-AVI2") (class "Default")
      (node (ref "H1") (pin "4") (pinfunction "4_4") (pintype "unspecified"))
      (node (ref "U1") (pin "6") (pinfunction "A2/GPIO28_6") (pintype "bidirectional"))
    )
    (net (code "15") (name "MCU-AVI3") (class "Default")
      (node (ref "H1") (pin "5") (pinfunction "5_5") (pintype "unspecified"))
      (node (ref "U1") (pin "9") (pinfunction "A5/GPIO13_9") (pintype "bidirectional"))
    )
    (net (code "16") (name "MCU-BLUELED") (class "Default")
      (node (ref "R29") (pin "1") (pinfunction "1_1") (pintype "input"))
      (node (ref "U1") (pin "8") (pinfunction "A4/GPIO12_8") (pintype "bidirectional"))
    )
    (net (code "17") (name "MCU-COIL") (class "Default")
      (node (ref "R12") (pin "2") (pinfunction "2_2") (pintype "input"))
      (node (ref "U1") (pin "25") (pinfunction "D7/GPIO19_25") (pintype "bidirectional"))
    )
    (net (code "18") (name "MCU-DPI") (class "Default")
      (node (ref "R30") (pin "2") (pinfunction "2_2") (pintype "input"))
      (node (ref "U1") (pin "5") (pinfunction "A1/GPIO27_5") (pintype "bidirectional"))
    )
    (net (code "19") (name "MCU-DPO") (class "Default")
      (node (ref "R23") (pin "1") (pinfunction "1_1") (pintype "input"))
      (node (ref "U1") (pin "24") (pinfunction "D6/GPIO18_24") (pintype "bidirectional"))
    )
    (net (code "20") (name "MCU-EXT1") (class "Default")
      (node (ref "H1") (pin "1") (pinfunction "1_1") (pintype "unspecified"))
      (node (ref "U1") (pin "23") (pinfunction "D5/GPIO17_23") (pintype "bidirectional"))
    )
    (net (code "21") (name "MCU-EXT2") (class "Default")
      (node (ref "H1") (pin "2") (pinfunction "2_2") (pintype "unspecified"))
      (node (ref "U1") (pin "26") (pinfunction "D8/GPIO20_26") (pintype "bidirectional"))
    )
    (net (code "22") (name "MCU-EXT3") (class "Default")
      (node (ref "H1") (pin "3") (pinfunction "3_3") (pintype "unspecified"))
      (node (ref "U1") (pin "27") (pinfunction "D9/GPIO21_27") (pintype "bidirectional"))
    )
    (net (code "23") (name "MCU-MISO") (class "Default")
      (node (ref "U1") (pin "30") (pinfunction "D12/GPIO4/CIPO_30") (pintype "bidirectional"))
    )
    (net (code "24") (name "MCU-MOSI") (class "Default")
      (node (ref "U1") (pin "29") (pinfunction "D11/GPIO7/COPI_29") (pintype "bidirectional"))
    )
    (net (code "25") (name "MCU-PD0") (class "Default")
      (node (ref "J2") (pin "2") (pinfunction "2_2") (pintype "unspecified"))
      (node (ref "U1") (pin "17") (pinfunction "RX_17") (pintype "bidirectional"))
    )
    (net (code "26") (name "MCU-PD1") (class "Default")
      (node (ref "J2") (pin "3") (pinfunction "3_3") (pintype "unspecified"))
      (node (ref "U1") (pin "16") (pinfunction "TX_16") (pintype "bidirectional"))
    )
    (net (code "27") (name "MCU-REDLED") (class "Default")
      (node (ref "R6") (pin "1") (pinfunction "1_1") (pintype "input"))
      (node (ref "U1") (pin "7") (pinfunction "A3/GPIO29_7") (pintype "bidirectional"))
    )
    (net (code "28") (name "MCU-RPM") (class "Default")
      (node (ref "C8") (pin "2") (pinfunction "2_2") (pintype "input"))
      (node (ref "D5") (pin "1") (pinfunction "C_1") (pintype "unspecified"))
      (node (ref "R3") (pin "2") (pinfunction "2_2") (pintype "input"))
      (node (ref "U1") (pin "21") (pinfunction "D3/GPIO15_21") (pintype "bidirectional"))
    )
    (net (code "29") (name "MCU-SCK") (class "Default")
      (node (ref "U1") (pin "1") (pinfunction "D13/GPIO6_1") (pintype "bidirectional"))
    )
    (net (code "30") (name "MCU-TOYOTA1") (class "Default")
      (node (ref "R13") (pin "1") (pinfunction "1_1") (pintype "input"))
      (node (ref "U1") (pin "20") (pinfunction "D2/GPIO25_20") (pintype "bidirectional"))
    )
    (net (code "31") (name "MCU-TOYOTA2") (class "Default")
      (node (ref "R14") (pin "1") (pinfunction "1_1") (pintype "input"))
      (node (ref "U1") (pin "22") (pinfunction "D4/GPIO26_22") (pintype "bidirectional"))
    )
    (net (code "32") (name "Net-(D3-C)") (class "Default")
      (node (ref "D3") (pin "1") (pinfunction "C_1") (pintype "unspecified"))
      (node (ref "Q2") (pin "1") (pinfunction "B_1") (pintype "unspecified"))
      (node (ref "R12") (pin "1") (pinfunction "1_1") (pintype "input"))
    )
    (net (code "33") (name "Net-(D4-A)") (class "Default")
      (node (ref "D4") (pin "2") (pinfunction "A_2") (pintype "unspecified"))
      (node (ref "D6") (pin "1") (pinfunction "C_1") (pintype "unspecified"))
      (node (ref "D7") (pin "2") (pinfunction "A_2") (pintype "unspecified"))
      (node (ref "Q1") (pin "2") (pinfunction "D_2") (pintype "unspecified"))
    )
    (net (code "34") (name "Net-(LED1-A)") (class "Default")
      (node (ref "LED1") (pin "2") (pinfunction "A_2") (pintype "unspecified"))
      (node (ref "R1") (pin "1") (pinfunction "1_1") (pintype "input"))
    )
    (net (code "35") (name "Net-(LED1-K)") (class "Default")
      (node (ref "LED1") (pin "1") (pinfunction "K_1") (pintype "unspecified"))
      (node (ref "Q1") (pin "1") (pinfunction "G_1") (pintype "unspecified"))
      (node (ref "Q2") (pin "3") (pinfunction "C_3") (pintype "unspecified"))
      (node (ref "R2") (pin "1") (pinfunction "1_1") (pintype "input"))
    )
    (net (code "36") (name "Net-(LED2-+)") (class "Default")
      (node (ref "LED2") (pin "2") (pinfunction "+_2") (pintype "unspecified"))
      (node (ref "LED3") (pin "2") (pinfunction "+_2") (pintype "unspecified"))
      (node (ref "LED4") (pin "2") (pinfunction "+_2") (pintype "unspecified"))
      (node (ref "LED5") (pin "2") (pinfunction "+_2") (pintype "unspecified"))
      (node (ref "R4") (pin "2") (pinfunction "2_2") (pintype "input"))
    )
    (net (code "37") (name "Net-(LED2--)") (class "Default")
      (node (ref "LED2") (pin "1") (pinfunction "-_1") (pintype "unspecified"))
      (node (ref "LED3") (pin "1") (pinfunction "-_1") (pintype "unspecified"))
      (node (ref "LED4") (pin "1") (pinfunction "-_1") (pintype "unspecified"))
      (node (ref "LED5") (pin "1") (pinfunction "-_1") (pintype "unspecified"))
      (node (ref "LED6") (pin "1") (pinfunction "-_1") (pintype "unspecified"))
      (node (ref "LED7") (pin "1") (pinfunction "-_1") (pintype "unspecified"))
      (node (ref "LED8") (pin "1") (pinfunction "-_1") (pintype "unspecified"))
      (node (ref "LED9") (pin "1") (pinfunction "-_1") (pintype "unspecified"))
      (node (ref "Q3") (pin "3") (pinfunction "C_3") (pintype "unspecified"))
    )
    (net (code "38") (name "Net-(LED6-+)") (class "Default")
      (node (ref "LED6") (pin "2") (pinfunction "+_2") (pintype "unspecified"))
      (node (ref "LED7") (pin "2") (pinfunction "+_2") (pintype "unspecified"))
      (node (ref "LED8") (pin "2") (pinfunction "+_2") (pintype "unspecified"))
      (node (ref "LED9") (pin "2") (pinfunction "+_2") (pintype "unspecified"))
      (node (ref "R9") (pin "1") (pinfunction "1_1") (pintype "input"))
    )
    (net (code "39") (name "Net-(LED12-A)") (class "Default")
      (node (ref "LED12") (pin "2") (pinfunction "A_2") (pintype "input"))
      (node (ref "R16") (pin "2") (pinfunction "2_2") (pintype "input"))
    )
    (net (code "40") (name "Net-(LED13-+)") (class "Default")
      (node (ref "LED13") (pin "2") (pinfunction "+_2") (pintype "unspecified"))
      (node (ref "LED14") (pin "2") (pinfunction "+_2") (pintype "unspecified"))
      (node (ref "LED15") (pin "2") (pinfunction "+_2") (pintype "unspecified"))
      (node (ref "LED16") (pin "2") (pinfunction "+_2") (pintype "unspecified"))
      (node (ref "R27") (pin "2") (pinfunction "2_2") (pintype "input"))
    )
    (net (code "41") (name "Net-(LED13--)") (class "Default")
      (node (ref "LED13") (pin "1") (pinfunction "-_1") (pintype "unspecified"))
      (node (ref "LED14") (pin "1") (pinfunction "-_1") (pintype "unspecified"))
      (node (ref "LED15") (pin "1") (pinfunction "-_1") (pintype "unspecified"))
      (node (ref "LED16") (pin "1") (pinfunction "-_1") (pintype "unspecified"))
      (node (ref "LED17") (pin "1") (pinfunction "-_1") (pintype "unspecified"))
      (node (ref "LED18") (pin "1") (pinfunction "-_1") (pintype "unspecified"))
      (node (ref "LED19") (pin "1") (pinfunction "-_1") (pintype "unspecified"))
      (node (ref "LED20") (pin "1") (pinfunction "-_1") (pintype "unspecified"))
      (node (ref "Q10") (pin "3") (pinfunction "C_3") (pintype "unspecified"))
    )
    (net (code "42") (name "Net-(LED17-+)") (class "Default")
      (node (ref "LED17") (pin "2") (pinfunction "+_2") (pintype "unspecified"))
      (node (ref "LED18") (pin "2") (pinfunction "+_2") (pintype "unspecified"))
      (node (ref "LED19") (pin "2") (pinfunction "+_2") (pintype "unspecified"))
      (node (ref "LED20") (pin "2") (pinfunction "+_2") (pintype "unspecified"))
      (node (ref "R28") (pin "1") (pinfunction "1_1") (pintype "input"))
    )
    (net (code "43") (name "Net-(Q3-B)") (class "Default")
      (node (ref "Q3") (pin "1") (pinfunction "B_1") (pintype "unspecified"))
      (node (ref "R6") (pin "2") (pinfunction "2_2") (pintype "input"))
    )
    (net (code "44") (name "Net-(Q4-B)") (class "Default")
      (node (ref "Q4") (pin "1") (pinfunction "B_1") (pintype "unspecified"))
      (node (ref "R13") (pin "2") (pinfunction "2_2") (pintype "input"))
    )
    (net (code "45") (name "Net-(Q5-B)") (class "Default")
      (node (ref "Q5") (pin "1") (pinfunction "B_1") (pintype "unspecified"))
      (node (ref "R14") (pin "2") (pinfunction "2_2") (pintype "input"))
    )
    (net (code "46") (name "Net-(Q8-B)") (class "Default")
      (node (ref "Q8") (pin "1") (pinfunction "B_1") (pintype "unspecified"))
      (node (ref "R23") (pin "2") (pinfunction "2_2") (pintype "input"))
    )
    (net (code "47") (name "Net-(Q10-B)") (class "Default")
      (node (ref "Q10") (pin "1") (pinfunction "B_1") (pintype "unspecified"))
      (node (ref "R29") (pin "2") (pinfunction "2_2") (pintype "input"))
    )
    (net (code "48") (name "Net-(U2-OUT)") (class "Default")
      (node (ref "C4") (pin "2") (pinfunction "2_2") (pintype "input"))
      (node (ref "C5") (pin "2") (pinfunction "2_2") (pintype "unspecified"))
      (node (ref "L1") (pin "1") (pinfunction "1_1") (pintype "unspecified"))
      (node (ref "U2") (pin "3") (pinfunction "OUT_3") (pintype "passive"))
    )
    (net (code "49") (name "RPM") (class "Default")
      (node (ref "C7") (pin "2") (pinfunction "2_2") (pintype "input"))
      (node (ref "CN3") (pin "5") (pinfunction "5_5") (pintype "unspecified"))
      (node (ref "R3") (pin "1") (pinfunction "1_1") (pintype "input"))
    )
    (net (code "50") (name "TOYOTA1") (class "Default")
      (node (ref "CN3") (pin "3") (pinfunction "3_3") (pintype "unspecified"))
      (node (ref "Q4") (pin "3") (pinfunction "C_3") (pintype "unspecified"))
    )
    (net (code "51") (name "TOYOTA2") (class "Default")
      (node (ref "CN3") (pin "4") (pinfunction "4_4") (pintype "unspecified"))
      (node (ref "Q5") (pin "3") (pinfunction "C_3") (pintype "unspecified"))
    )
    (net (code "52") (name "unconnected-(U1-+3V3-Pad2)") (class "Default")
      (node (ref "U1") (pin "2") (pinfunction "+3V3_2") (pintype "bidirectional+no_connect"))
    )
    (net (code "53") (name "unconnected-(U1-A6-Pad10)") (class "Default")
      (node (ref "U1") (pin "10") (pinfunction "A6_10") (pintype "bidirectional"))
    )
    (net (code "54") (name "unconnected-(U1-AREF-Pad3)") (class "Default")
      (node (ref "U1") (pin "3") (pinfunction "AREF_3") (pintype "bidirectional+no_connect"))
    )
    (net (code "55") (name "unconnected-(U1-QSPI_RESET-Pad13)") (class "Default")
      (node (ref "U1") (pin "13") (pinfunction "QSPI_RESET_13") (pintype "input+no_connect"))
    )
    (net (code "56") (name "unconnected-(U1-RESET-Pad18)") (class "Default")
      (node (ref "U1") (pin "18") (pinfunction "RESET_18") (pintype "input+no_connect"))
    )
    (net (code "57") (name "unconnected-(U1-VIN-Pad15)") (class "Default")
      (node (ref "U1") (pin "15") (pinfunction "VIN_15") (pintype "bidirectional+no_connect"))
    )
  )
)
